# Board_1.net
KiCad netlist of a schematic drawn in EAGLE
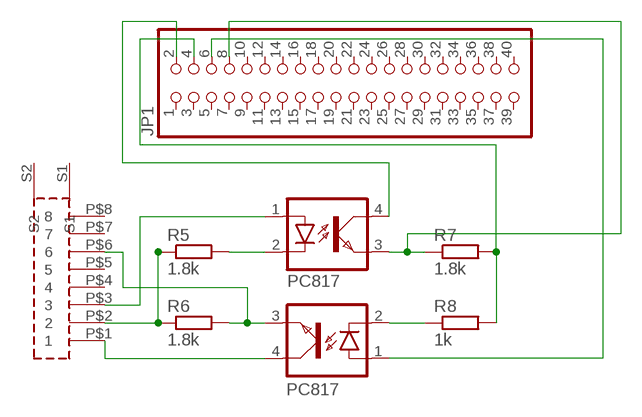
[diagram p0: schematic, sheet 1]

(export (version "E")
  (design (tool "Eeschema 10.0.6"))
  (components
    (comp (ref "JP1")
      (value "PINHD-2X20-BIG")
      (footprint "eagle-import:2X20-BIG")
      (libsource (lib "eagle-import") (part "PINHD-2X20-BIG"))
    )
    (comp (ref "OK1")
      (value "PC817")
      (footprint "eagle-import:DIL04")
      (fields (field (name "MPN") "PC817X4J000F"))
      (libsource (lib "eagle-import") (part "PC817"))
    )
    (comp (ref "OK2")
      (value "PC817")
      (footprint "eagle-import:DIL04")
      (fields (field (name "MPN") "PC817X4J000F"))
      (libsource (lib "eagle-import") (part "PC817"))
    )
    (comp (ref "R5")
      (value "1.8k")
      (footprint "eagle-import:0207_10")
      (libsource (lib "eagle-import") (part "R-EU_0207/10"))
    )
    (comp (ref "R6")
      (value "1.8k")
      (footprint "eagle-import:0207_10")
      (libsource (lib "eagle-import") (part "R-EU_0207/10"))
    )
    (comp (ref "R7")
      (value "1.8k")
      (footprint "eagle-import:0207_10")
      (libsource (lib "eagle-import") (part "R-EU_0207/10"))
    )
    (comp (ref "R8")
      (value "1k")
      (footprint "eagle-import:0207_10")
      (libsource (lib "eagle-import") (part "R-EU_0207/10"))
    )
    (comp (ref "U$1")
      (value "RJ-45")
      (footprint "eagle-import:RJ-45")
      (libsource (lib "eagle-import") (part "RJ-45"))
    )
  )
  (nets
    (net (code "1") (name "Net-(JP1-Pad4)") (class "Default")
      (node (ref "JP1") (pin "4") (pinfunction "4_4") (pintype "passive"))
      (node (ref "R7") (pin "2") (pinfunction "2_2") (pintype "passive"))
      (node (ref "R8") (pin "2") (pinfunction "2_2") (pintype "passive"))
    )
    (net (code "2") (name "Net-(OK1-A)") (class "Default")
      (node (ref "OK1") (pin "1") (pinfunction "A_1") (pintype "passive"))
      (node (ref "U$1") (pin "P$3") (pinfunction "3_P$3") (pintype "bidirectional"))
    )
    (net (code "3") (name "Net-(OK1-C)") (class "Default")
      (node (ref "OK1") (pin "2") (pinfunction "C_2") (pintype "passive"))
      (node (ref "R5") (pin "2") (pinfunction "2_2") (pintype "passive"))
    )
    (net (code "4") (name "Net-(OK1-COL)") (class "Default")
      (node (ref "JP1") (pin "2") (pinfunction "2_2") (pintype "passive"))
      (node (ref "OK1") (pin "4") (pinfunction "COL_4") (pintype "passive"))
    )
    (net (code "5") (name "Net-(OK1-EMIT)") (class "Default")
      (node (ref "JP1") (pin "8") (pinfunction "8_8") (pintype "passive"))
      (node (ref "OK1") (pin "3") (pinfunction "EMIT_3") (pintype "passive"))
      (node (ref "R7") (pin "1") (pinfunction "1_1") (pintype "passive"))
    )
    (net (code "6") (name "Net-(OK2-A)") (class "Default")
      (node (ref "JP1") (pin "6") (pinfunction "6_6") (pintype "passive"))
      (node (ref "OK2") (pin "1") (pinfunction "A_1") (pintype "passive"))
    )
    (net (code "7") (name "Net-(OK2-C)") (class "Default")
      (node (ref "OK2") (pin "2") (pinfunction "C_2") (pintype "passive"))
      (node (ref "R8") (pin "1") (pinfunction "1_1") (pintype "passive"))
    )
    (net (code "8") (name "Net-(OK2-COL)") (class "Default")
      (node (ref "OK2") (pin "4") (pinfunction "COL_4") (pintype "passive"))
      (node (ref "U$1") (pin "P$1") (pinfunction "1_P$1") (pintype "bidirectional"))
    )
    (net (code "9") (name "Net-(OK2-EMIT)") (class "Default")
      (node (ref "OK2") (pin "3") (pinfunction "EMIT_3") (pintype "passive"))
      (node (ref "R6") (pin "2") (pinfunction "2_2") (pintype "passive"))
      (node (ref "U$1") (pin "P$6") (pinfunction "6_P$6") (pintype "bidirectional"))
    )
    (net (code "10") (name "Net-(U$1-2)") (class "Default")
      (node (ref "R5") (pin "1") (pinfunction "1_1") (pintype "passive"))
      (node (ref "R6") (pin "1") (pinfunction "1_1") (pintype "passive"))
      (node (ref "U$1") (pin "P$2") (pinfunction "2_P$2") (pintype "bidirectional"))
    )
    (net (code "11") (name "unconnected-(JP1-Pad1)") (class "Default")
      (node (ref "JP1") (pin "1") (pinfunction "1_1") (pintype "passive"))
    )
    (net (code "12") (name "unconnected-(JP1-Pad3)") (class "Default")
      (node (ref "JP1") (pin "3") (pinfunction "3_3") (pintype "passive"))
    )
    (net (code "13") (name "unconnected-(JP1-Pad5)") (class "Default")
      (node (ref "JP1") (pin "5") (pinfunction "5_5") (pintype "passive"))
    )
    (net (code "14") (name "unconnected-(JP1-Pad7)") (class "Default")
      (node (ref "JP1") (pin "7") (pinfunction "7_7") (pintype "passive"))
    )
    (net (code "15") (name "unconnected-(JP1-Pad9)") (class "Default")
      (node (ref "JP1") (pin "9") (pinfunction "9_9") (pintype "passive"))
    )
    (net (code "16") (name "unconnected-(JP1-Pad10)") (class "Default")
      (node (ref "JP1") (pin "10") (pinfunction "10_10") (pintype "passive"))
    )
    (net (code "17") (name "unconnected-(JP1-Pad11)") (class "Default")
      (node (ref "JP1") (pin "11") (pinfunction "11_11") (pintype "passive"))
    )
    (net (code "18") (name "unconnected-(JP1-Pad12)") (class "Default")
      (node (ref "JP1") (pin "12") (pinfunction "12_12") (pintype "passive"))
    )
    (net (code "19") (name "unconnected-(JP1-Pad13)") (class "Default")
      (node (ref "JP1") (pin "13") (pinfunction "13_13") (pintype "passive"))
    )
    (net (code "20") (name "unconnected-(JP1-Pad14)") (class "Default")
      (node (ref "JP1") (pin "14") (pinfunction "14_14") (pintype "passive"))
    )
    (net (code "21") (name "unconnected-(JP1-Pad15)") (class "Default")
      (node (ref "JP1") (pin "15") (pinfunction "15_15") (pintype "passive"))
    )
    (net (code "22") (name "unconnected-(JP1-Pad16)") (class "Default")
      (node (ref "JP1") (pin "16") (pinfunction "16_16") (pintype "passive"))
    )
    (net (code "23") (name "unconnected-(JP1-Pad17)") (class "Default")
      (node (ref "JP1") (pin "17") (pinfunction "17_17") (pintype "passive"))
    )
    (net (code "24") (name "unconnected-(JP1-Pad18)") (class "Default")
      (node (ref "JP1") (pin "18") (pinfunction "18_18") (pintype "passive"))
    )
    (net (code "25") (name "unconnected-(JP1-Pad19)") (class "Default")
      (node (ref "JP1") (pin "19") (pinfunction "19_19") (pintype "passive"))
    )
    (net (code "26") (name "unconnected-(JP1-Pad20)") (class "Default")
      (node (ref "JP1") (pin "20") (pinfunction "20_20") (pintype "passive"))
    )
    (net (code "27") (name "unconnected-(JP1-Pad21)") (class "Default")
      (node (ref "JP1") (pin "21") (pinfunction "21_21") (pintype "passive"))
    )
    (net (code "28") (name "unconnected-(JP1-Pad22)") (class "Default")
      (node (ref "JP1") (pin "22") (pinfunction "22_22") (pintype "passive"))
    )
    (net (code "29") (name "unconnected-(JP1-Pad23)") (class "Default")
      (node (ref "JP1") (pin "23") (pinfunction "23_23") (pintype "passive"))
    )
    (net (code "30") (name "unconnected-(JP1-Pad24)") (class "Default")
      (node (ref "JP1") (pin "24") (pinfunction "24_24") (pintype "passive"))
    )
    (net (code "31") (name "unconnected-(JP1-Pad25)") (class "Default")
      (node (ref "JP1") (pin "25") (pinfunction "25_25") (pintype "passive"))
    )
    (net (code "32") (name "unconnected-(JP1-Pad26)") (class "Default")
      (node (ref "JP1") (pin "26") (pinfunction "26_26") (pintype "passive"))
    )
    (net (code "33") (name "unconnected-(JP1-Pad27)") (class "Default")
      (node (ref "JP1") (pin "27") (pinfunction "27_27") (pintype "passive"))
    )
    (net (code "34") (name "unconnected-(JP1-Pad28)") (class "Default")
      (node (ref "JP1") (pin "28") (pinfunction "28_28") (pintype "passive"))
    )
    (net (code "35") (name "unconnected-(JP1-Pad29)") (class "Default")
      (node (ref "JP1") (pin "29") (pinfunction "29_29") (pintype "passive"))
    )
    (net (code "36") (name "unconnected-(JP1-Pad30)") (class "Default")
      (node (ref "JP1") (pin "30") (pinfunction "30_30") (pintype "passive"))
    )
    (net (code "37") (name "unconnected-(JP1-Pad31)") (class "Default")
      (node (ref "JP1") (pin "31") (pinfunction "31_31") (pintype "passive"))
    )
    (net (code "38") (name "unconnected-(JP1-Pad32)") (class "Default")
      (node (ref "JP1") (pin "32") (pinfunction "32_32") (pintype "passive"))
    )
    (net (code "39") (name "unconnected-(JP1-Pad33)") (class "Default")
      (node (ref "JP1") (pin "33") (pinfunction "33_33") (pintype "passive"))
    )
    (net (code "40") (name "unconnected-(JP1-Pad34)") (class "Default")
      (node (ref "JP1") (pin "34") (pinfunction "34_34") (pintype "passive"))
    )
    (net (code "41") (name "unconnected-(JP1-Pad35)") (class "Default")
      (node (ref "JP1") (pin "35") (pinfunction "35_35") (pintype "passive"))
    )
    (net (code "42") (name "unconnected-(JP1-Pad36)") (class "Default")
      (node (ref "JP1") (pin "36") (pinfunction "36_36") (pintype "passive"))
    )
    (net (code "43") (name "unconnected-(JP1-Pad37)") (class "Default")
      (node (ref "JP1") (pin "37") (pinfunction "37_37") (pintype "passive"))
    )
    (net (code "44") (name "unconnected-(JP1-Pad38)") (class "Default")
      (node (ref "JP1") (pin "38") (pinfunction "38_38") (pintype "passive"))
    )
    (net (code "45") (name "unconnected-(JP1-Pad39)") (class "Default")
      (node (ref "JP1") (pin "39") (pinfunction "39_39") (pintype "passive"))
    )
    (net (code "46") (name "unconnected-(JP1-Pad40)") (class "Default")
      (node (ref "JP1") (pin "40") (pinfunction "40_40") (pintype "passive"))
    )
    (net (code "47") (name "unconnected-(U$1-4-PadP$4)") (class "Default")
      (node (ref "U$1") (pin "P$4") (pinfunction "4_P$4") (pintype "bidirectional"))
    )
    (net (code "48") (name "unconnected-(U$1-5-PadP$5)") (class "Default")
      (node (ref "U$1") (pin "P$5") (pinfunction "5_P$5") (pintype "bidirectional"))
    )
    (net (code "49") (name "unconnected-(U$1-7-PadP$7)") (class "Default")
      (node (ref "U$1") (pin "P$7") (pinfunction "7_P$7") (pintype "bidirectional"))
    )
    (net (code "50") (name "unconnected-(U$1-8-PadP$8)") (class "Default")
      (node (ref "U$1") (pin "P$8") (pinfunction "8_P$8") (pintype "bidirectional"))
    )
    (net (code "51") (name "unconnected-(U$1-PadS1)") (class "Default")
      (node (ref "U$1") (pin "S1") (pinfunction "S1_S1") (pintype "bidirectional"))
    )
    (net (code "52") (name "unconnected-(U$1-PadS2)") (class "Default")
      (node (ref "U$1") (pin "S2") (pinfunction "S2_S2") (pintype "bidirectional"))
    )
  )
)
